# rc2014_6522.net
KiCad netlist of a schematic drawn in EAGLE
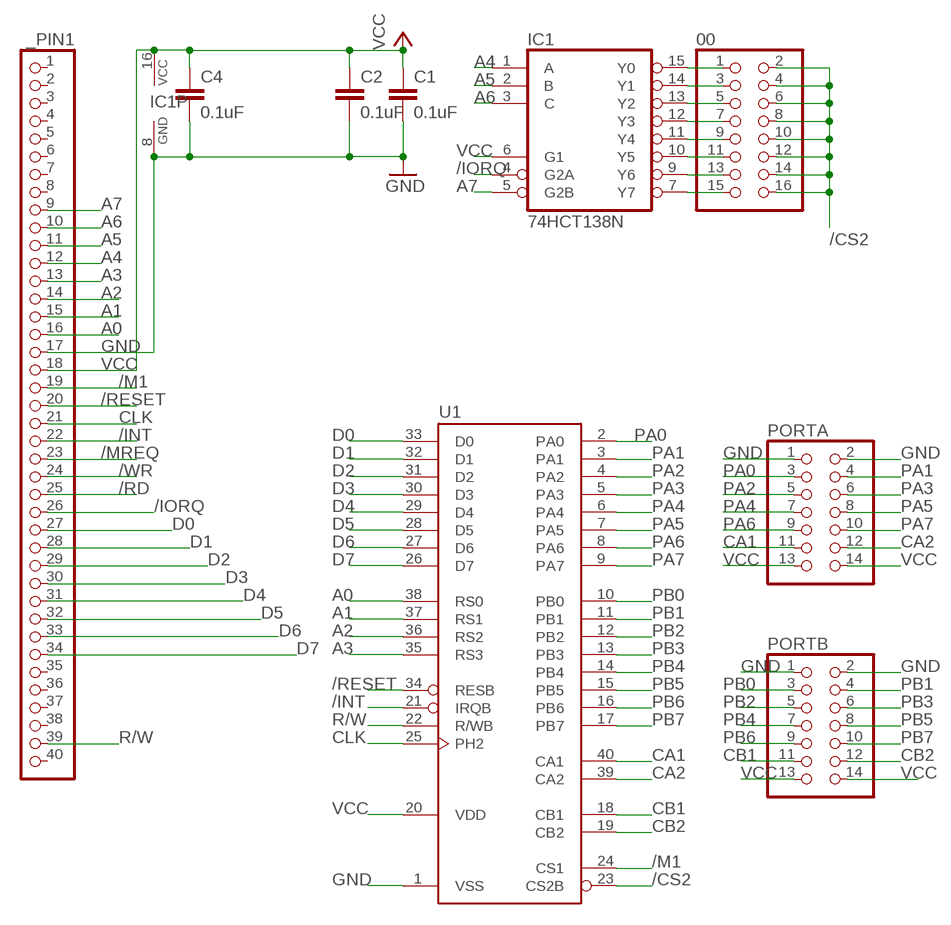
[diagram p0: schematic, sheet 1]

(export (version "E")
  (design (tool "Eeschema 10.0.6"))
  (components
    (comp (ref "00")
      (value "PINHD-2X8")
      (footprint "eagle-import:2X08")
      (libsource (lib "eagle-import") (part "PINHD-2X8"))
    )
    (comp (ref "C1")
      (value "0.1uF")
      (footprint "eagle-import:C050-024X044")
      (libsource (lib "eagle-import") (part "C-EU050-024X044"))
    )
    (comp (ref "C2")
      (value "0.1uF")
      (footprint "eagle-import:C050-024X044")
      (libsource (lib "eagle-import") (part "C-EU050-024X044"))
    )
    (comp (ref "C4")
      (value "0.1uF")
      (footprint "eagle-import:C050-024X044")
      (libsource (lib "eagle-import") (part "C-EU050-024X044"))
    )
    (comp (ref "IC1")
      (value "74HCT138N")
      (footprint "eagle-import:DIL16")
      (libsource (lib "eagle-import") (part "74138NHCT"))
    )
    (comp (ref "PORTA")
      (value "PINHD-2X7")
      (footprint "eagle-import:2X07")
      (libsource (lib "eagle-import") (part "PINHD-2X7"))
    )
    (comp (ref "PORTB")
      (value "PINHD-2X7")
      (footprint "eagle-import:2X07")
      (libsource (lib "eagle-import") (part "PINHD-2X7"))
    )
    (comp (ref "U1")
      (value "G65SC22P")
      (footprint "eagle-import:DIP-40")
      (libsource (lib "eagle-import") (part "G65SC22P"))
    )
    (comp (ref "_PIN1")
      (value "PINHD-1X40")
      (footprint "eagle-import:1X40")
      (libsource (lib "eagle-import") (part "PINHD-1X40"))
    )
  )
  (nets
    (net (code "1") (name "/A0") (class "Default")
      (node (ref "U1") (pin "38") (pinfunction "RS0_38") (pintype "input"))
      (node (ref "_PIN1") (pin "16") (pinfunction "16_16") (pintype "passive"))
    )
    (net (code "2") (name "/A1") (class "Default")
      (node (ref "U1") (pin "37") (pinfunction "RS1_37") (pintype "input"))
      (node (ref "_PIN1") (pin "15") (pinfunction "15_15") (pintype "passive"))
    )
    (net (code "3") (name "/A2") (class "Default")
      (node (ref "U1") (pin "36") (pinfunction "RS2_36") (pintype "input"))
      (node (ref "_PIN1") (pin "14") (pinfunction "14_14") (pintype "passive"))
    )
    (net (code "4") (name "/A3") (class "Default")
      (node (ref "U1") (pin "35") (pinfunction "RS3_35") (pintype "input"))
      (node (ref "_PIN1") (pin "13") (pinfunction "13_13") (pintype "passive"))
    )
    (net (code "5") (name "/A4") (class "Default")
      (node (ref "IC1") (pin "1") (pinfunction "A_1") (pintype "input"))
      (node (ref "_PIN1") (pin "12") (pinfunction "12_12") (pintype "passive"))
    )
    (net (code "6") (name "/A5") (class "Default")
      (node (ref "IC1") (pin "2") (pinfunction "B_2") (pintype "input"))
      (node (ref "_PIN1") (pin "11") (pinfunction "11_11") (pintype "passive"))
    )
    (net (code "7") (name "/A6") (class "Default")
      (node (ref "IC1") (pin "3") (pinfunction "C_3") (pintype "input"))
      (node (ref "_PIN1") (pin "10") (pinfunction "10_10") (pintype "passive"))
    )
    (net (code "8") (name "/A7") (class "Default")
      (node (ref "IC1") (pin "5") (pinfunction "G2B_5") (pintype "input"))
      (node (ref "_PIN1") (pin "9") (pinfunction "9_9") (pintype "passive"))
    )
    (net (code "9") (name "/CA1") (class "Default")
      (node (ref "PORTA") (pin "11") (pinfunction "11_11") (pintype "passive"))
      (node (ref "U1") (pin "40") (pinfunction "CA1_40") (pintype "bidirectional"))
    )
    (net (code "10") (name "/CA2") (class "Default")
      (node (ref "PORTA") (pin "12") (pinfunction "12_12") (pintype "passive"))
      (node (ref "U1") (pin "39") (pinfunction "CA2_39") (pintype "bidirectional"))
    )
    (net (code "11") (name "/CB1") (class "Default")
      (node (ref "PORTB") (pin "11") (pinfunction "11_11") (pintype "passive"))
      (node (ref "U1") (pin "18") (pinfunction "CB1_18") (pintype "bidirectional"))
    )
    (net (code "12") (name "/CB2") (class "Default")
      (node (ref "PORTB") (pin "12") (pinfunction "12_12") (pintype "passive"))
      (node (ref "U1") (pin "19") (pinfunction "CB2_19") (pintype "bidirectional"))
    )
    (net (code "13") (name "/CLK") (class "Default")
      (node (ref "U1") (pin "25") (pinfunction "PH2_25") (pintype "input"))
      (node (ref "_PIN1") (pin "21") (pinfunction "21_21") (pintype "passive"))
    )
    (net (code "14") (name "/D0") (class "Default")
      (node (ref "U1") (pin "33") (pinfunction "D0_33") (pintype "bidirectional"))
      (node (ref "_PIN1") (pin "27") (pinfunction "27_27") (pintype "passive"))
    )
    (net (code "15") (name "/D1") (class "Default")
      (node (ref "U1") (pin "32") (pinfunction "D1_32") (pintype "bidirectional"))
      (node (ref "_PIN1") (pin "28") (pinfunction "28_28") (pintype "passive"))
    )
    (net (code "16") (name "/D2") (class "Default")
      (node (ref "U1") (pin "31") (pinfunction "D2_31") (pintype "bidirectional"))
      (node (ref "_PIN1") (pin "29") (pinfunction "29_29") (pintype "passive"))
    )
    (net (code "17") (name "/D3") (class "Default")
      (node (ref "U1") (pin "30") (pinfunction "D3_30") (pintype "bidirectional"))
      (node (ref "_PIN1") (pin "30") (pinfunction "30_30") (pintype "passive"))
    )
    (net (code "18") (name "/D4") (class "Default")
      (node (ref "U1") (pin "29") (pinfunction "D4_29") (pintype "bidirectional"))
      (node (ref "_PIN1") (pin "31") (pinfunction "31_31") (pintype "passive"))
    )
    (net (code "19") (name "/D5") (class "Default")
      (node (ref "U1") (pin "28") (pinfunction "D5_28") (pintype "bidirectional"))
      (node (ref "_PIN1") (pin "32") (pinfunction "32_32") (pintype "passive"))
    )
    (net (code "20") (name "/D6") (class "Default")
      (node (ref "U1") (pin "27") (pinfunction "D6_27") (pintype "bidirectional"))
      (node (ref "_PIN1") (pin "33") (pinfunction "33_33") (pintype "passive"))
    )
    (net (code "21") (name "/D7") (class "Default")
      (node (ref "U1") (pin "26") (pinfunction "D7_26") (pintype "bidirectional"))
      (node (ref "_PIN1") (pin "34") (pinfunction "34_34") (pintype "passive"))
    )
    (net (code "22") (name "/PA0") (class "Default")
      (node (ref "PORTA") (pin "3") (pinfunction "3_3") (pintype "passive"))
      (node (ref "U1") (pin "2") (pinfunction "PA0_2") (pintype "bidirectional"))
    )
    (net (code "23") (name "/PA1") (class "Default")
      (node (ref "PORTA") (pin "4") (pinfunction "4_4") (pintype "passive"))
      (node (ref "U1") (pin "3") (pinfunction "PA1_3") (pintype "bidirectional"))
    )
    (net (code "24") (name "/PA2") (class "Default")
      (node (ref "PORTA") (pin "5") (pinfunction "5_5") (pintype "passive"))
      (node (ref "U1") (pin "4") (pinfunction "PA2_4") (pintype "bidirectional"))
    )
    (net (code "25") (name "/PA3") (class "Default")
      (node (ref "PORTA") (pin "6") (pinfunction "6_6") (pintype "passive"))
      (node (ref "U1") (pin "5") (pinfunction "PA3_5") (pintype "bidirectional"))
    )
    (net (code "26") (name "/PA4") (class "Default")
      (node (ref "PORTA") (pin "7") (pinfunction "7_7") (pintype "passive"))
      (node (ref "U1") (pin "6") (pinfunction "PA4_6") (pintype "bidirectional"))
    )
    (net (code "27") (name "/PA5") (class "Default")
      (node (ref "PORTA") (pin "8") (pinfunction "8_8") (pintype "passive"))
      (node (ref "U1") (pin "7") (pinfunction "PA5_7") (pintype "bidirectional"))
    )
    (net (code "28") (name "/PA6") (class "Default")
      (node (ref "PORTA") (pin "9") (pinfunction "9_9") (pintype "passive"))
      (node (ref "U1") (pin "8") (pinfunction "PA6_8") (pintype "bidirectional"))
    )
    (net (code "29") (name "/PA7") (class "Default")
      (node (ref "PORTA") (pin "10") (pinfunction "10_10") (pintype "passive"))
      (node (ref "U1") (pin "9") (pinfunction "PA7_9") (pintype "bidirectional"))
    )
    (net (code "30") (name "/PB0") (class "Default")
      (node (ref "PORTB") (pin "3") (pinfunction "3_3") (pintype "passive"))
      (node (ref "U1") (pin "10") (pinfunction "PB0_10") (pintype "bidirectional"))
    )
    (net (code "31") (name "/PB1") (class "Default")
      (node (ref "PORTB") (pin "4") (pinfunction "4_4") (pintype "passive"))
      (node (ref "U1") (pin "11") (pinfunction "PB1_11") (pintype "bidirectional"))
    )
    (net (code "32") (name "/PB2") (class "Default")
      (node (ref "PORTB") (pin "5") (pinfunction "5_5") (pintype "passive"))
      (node (ref "U1") (pin "12") (pinfunction "PB2_12") (pintype "bidirectional"))
    )
    (net (code "33") (name "/PB3") (class "Default")
      (node (ref "PORTB") (pin "6") (pinfunction "6_6") (pintype "passive"))
      (node (ref "U1") (pin "13") (pinfunction "PB3_13") (pintype "bidirectional"))
    )
    (net (code "34") (name "/PB4") (class "Default")
      (node (ref "PORTB") (pin "7") (pinfunction "7_7") (pintype "passive"))
      (node (ref "U1") (pin "14") (pinfunction "PB4_14") (pintype "bidirectional"))
    )
    (net (code "35") (name "/PB5") (class "Default")
      (node (ref "PORTB") (pin "8") (pinfunction "8_8") (pintype "passive"))
      (node (ref "U1") (pin "15") (pinfunction "PB5_15") (pintype "bidirectional"))
    )
    (net (code "36") (name "/PB6") (class "Default")
      (node (ref "PORTB") (pin "9") (pinfunction "9_9") (pintype "passive"))
      (node (ref "U1") (pin "16") (pinfunction "PB6_16") (pintype "bidirectional"))
    )
    (net (code "37") (name "/PB7") (class "Default")
      (node (ref "PORTB") (pin "10") (pinfunction "10_10") (pintype "passive"))
      (node (ref "U1") (pin "17") (pinfunction "PB7_17") (pintype "bidirectional"))
    )
    (net (code "38") (name "/R{slash}W") (class "Default")
      (node (ref "U1") (pin "22") (pinfunction "R/WB_22") (pintype "input"))
      (node (ref "_PIN1") (pin "39") (pinfunction "39_39") (pintype "passive"))
    )
    (net (code "39") (name "/{slash}CS2") (class "Default")
      (node (ref "00") (pin "10") (pinfunction "10_10") (pintype "passive"))
      (node (ref "00") (pin "12") (pinfunction "12_12") (pintype "passive"))
      (node (ref "00") (pin "14") (pinfunction "14_14") (pintype "passive"))
      (node (ref "00") (pin "16") (pinfunction "16_16") (pintype "passive"))
      (node (ref "00") (pin "2") (pinfunction "2_2") (pintype "passive"))
      (node (ref "00") (pin "4") (pinfunction "4_4") (pintype "passive"))
      (node (ref "00") (pin "6") (pinfunction "6_6") (pintype "passive"))
      (node (ref "00") (pin "8") (pinfunction "8_8") (pintype "passive"))
      (node (ref "U1") (pin "23") (pinfunction "CS2B_23") (pintype "input"))
    )
    (net (code "40") (name "/{slash}INT") (class "Default")
      (node (ref "U1") (pin "21") (pinfunction "IRQB_21") (pintype "output"))
      (node (ref "_PIN1") (pin "22") (pinfunction "22_22") (pintype "passive"))
    )
    (net (code "41") (name "/{slash}IORQ") (class "Default")
      (node (ref "IC1") (pin "4") (pinfunction "G2A_4") (pintype "input"))
      (node (ref "_PIN1") (pin "26") (pinfunction "26_26") (pintype "passive"))
    )
    (net (code "42") (name "/{slash}M1") (class "Default")
      (node (ref "U1") (pin "24") (pinfunction "CS1_24") (pintype "input"))
      (node (ref "_PIN1") (pin "19") (pinfunction "19_19") (pintype "passive"))
    )
    (net (code "43") (name "/{slash}MREQ") (class "Default")
      (node (ref "_PIN1") (pin "23") (pinfunction "23_23") (pintype "passive"))
    )
    (net (code "44") (name "/{slash}RD") (class "Default")
      (node (ref "_PIN1") (pin "25") (pinfunction "25_25") (pintype "passive"))
    )
    (net (code "45") (name "/{slash}RESET") (class "Default")
      (node (ref "U1") (pin "34") (pinfunction "RESB_34") (pintype "input"))
      (node (ref "_PIN1") (pin "20") (pinfunction "20_20") (pintype "passive"))
    )
    (net (code "46") (name "/{slash}WR") (class "Default")
      (node (ref "_PIN1") (pin "24") (pinfunction "24_24") (pintype "passive"))
    )
    (net (code "47") (name "GND") (class "Default")
      (node (ref "C1") (pin "2") (pinfunction "2_2") (pintype "passive"))
      (node (ref "C2") (pin "2") (pinfunction "2_2") (pintype "passive"))
      (node (ref "C4") (pin "2") (pinfunction "2_2") (pintype "passive"))
      (node (ref "IC1") (pin "8") (pinfunction "GND_8") (pintype "power_in"))
      (node (ref "PORTA") (pin "1") (pinfunction "1_1") (pintype "passive"))
      (node (ref "PORTA") (pin "2") (pinfunction "2_2") (pintype "passive"))
      (node (ref "PORTB") (pin "1") (pinfunction "1_1") (pintype "passive"))
      (node (ref "PORTB") (pin "2") (pinfunction "2_2") (pintype "passive"))
      (node (ref "U1") (pin "1") (pinfunction "VSS_1") (pintype "power_in"))
      (node (ref "_PIN1") (pin "17") (pinfunction "17_17") (pintype "passive"))
    )
    (net (code "48") (name "Net-(IC1A-Y0)") (class "Default")
      (node (ref "00") (pin "1") (pinfunction "1_1") (pintype "passive"))
      (node (ref "IC1") (pin "15") (pinfunction "Y0_15") (pintype "output"))
    )
    (net (code "49") (name "Net-(IC1A-Y1)") (class "Default")
      (node (ref "00") (pin "3") (pinfunction "3_3") (pintype "passive"))
      (node (ref "IC1") (pin "14") (pinfunction "Y1_14") (pintype "output"))
    )
    (net (code "50") (name "Net-(IC1A-Y2)") (class "Default")
      (node (ref "00") (pin "5") (pinfunction "5_5") (pintype "passive"))
      (node (ref "IC1") (pin "13") (pinfunction "Y2_13") (pintype "output"))
    )
    (net (code "51") (name "Net-(IC1A-Y3)") (class "Default")
      (node (ref "00") (pin "7") (pinfunction "7_7") (pintype "passive"))
      (node (ref "IC1") (pin "12") (pinfunction "Y3_12") (pintype "output"))
    )
    (net (code "52") (name "Net-(IC1A-Y4)") (class "Default")
      (node (ref "00") (pin "9") (pinfunction "9_9") (pintype "passive"))
      (node (ref "IC1") (pin "11") (pinfunction "Y4_11") (pintype "output"))
    )
    (net (code "53") (name "Net-(IC1A-Y5)") (class "Default")
      (node (ref "00") (pin "11") (pinfunction "11_11") (pintype "passive"))
      (node (ref "IC1") (pin "10") (pinfunction "Y5_10") (pintype "output"))
    )
    (net (code "54") (name "Net-(IC1A-Y6)") (class "Default")
      (node (ref "00") (pin "13") (pinfunction "13_13") (pintype "passive"))
      (node (ref "IC1") (pin "9") (pinfunction "Y6_9") (pintype "output"))
    )
    (net (code "55") (name "Net-(IC1A-Y7)") (class "Default")
      (node (ref "00") (pin "15") (pinfunction "15_15") (pintype "passive"))
      (node (ref "IC1") (pin "7") (pinfunction "Y7_7") (pintype "output"))
    )
    (net (code "56") (name "VCC") (class "Default")
      (node (ref "C1") (pin "1") (pinfunction "1_1") (pintype "passive"))
      (node (ref "C2") (pin "1") (pinfunction "1_1") (pintype "passive"))
      (node (ref "C4") (pin "1") (pinfunction "1_1") (pintype "passive"))
      (node (ref "IC1") (pin "16") (pinfunction "VCC_16") (pintype "power_in"))
      (node (ref "IC1") (pin "6") (pinfunction "G1_6") (pintype "input"))
      (node (ref "PORTA") (pin "13") (pinfunction "13_13") (pintype "passive"))
      (node (ref "PORTA") (pin "14") (pinfunction "14_14") (pintype "passive"))
      (node (ref "PORTB") (pin "13") (pinfunction "13_13") (pintype "passive"))
      (node (ref "PORTB") (pin "14") (pinfunction "14_14") (pintype "passive"))
      (node (ref "U1") (pin "20") (pinfunction "VDD_20") (pintype "power_in"))
      (node (ref "_PIN1") (pin "18") (pinfunction "18_18") (pintype "passive"))
    )
    (net (code "57") (name "unconnected-(_PIN1-Pad1)") (class "Default")
      (node (ref "_PIN1") (pin "1") (pinfunction "1_1") (pintype "passive"))
    )
    (net (code "58") (name "unconnected-(_PIN1-Pad2)") (class "Default")
      (node (ref "_PIN1") (pin "2") (pinfunction "2_2") (pintype "passive"))
    )
    (net (code "59") (name "unconnected-(_PIN1-Pad3)") (class "Default")
      (node (ref "_PIN1") (pin "3") (pinfunction "3_3") (pintype "passive"))
    )
    (net (code "60") (name "unconnected-(_PIN1-Pad4)") (class "Default")
      (node (ref "_PIN1") (pin "4") (pinfunction "4_4") (pintype "passive"))
    )
    (net (code "61") (name "unconnected-(_PIN1-Pad5)") (class "Default")
      (node (ref "_PIN1") (pin "5") (pinfunction "5_5") (pintype "passive"))
    )
    (net (code "62") (name "unconnected-(_PIN1-Pad6)") (class "Default")
      (node (ref "_PIN1") (pin "6") (pinfunction "6_6") (pintype "passive"))
    )
    (net (code "63") (name "unconnected-(_PIN1-Pad7)") (class "Default")
      (node (ref "_PIN1") (pin "7") (pinfunction "7_7") (pintype "passive"))
    )
    (net (code "64") (name "unconnected-(_PIN1-Pad8)") (class "Default")
      (node (ref "_PIN1") (pin "8") (pinfunction "8_8") (pintype "passive"))
    )
    (net (code "65") (name "unconnected-(_PIN1-Pad35)") (class "Default")
      (node (ref "_PIN1") (pin "35") (pinfunction "35_35") (pintype "passive"))
    )
    (net (code "66") (name "unconnected-(_PIN1-Pad36)") (class "Default")
      (node (ref "_PIN1") (pin "36") (pinfunction "36_36") (pintype "passive"))
    )
    (net (code "67") (name "unconnected-(_PIN1-Pad37)") (class "Default")
      (node (ref "_PIN1") (pin "37") (pinfunction "37_37") (pintype "passive"))
    )
    (net (code "68") (name "unconnected-(_PIN1-Pad38)") (class "Default")
      (node (ref "_PIN1") (pin "38") (pinfunction "38_38") (pintype "passive"))
    )
    (net (code "69") (name "unconnected-(_PIN1-Pad40)") (class "Default")
      (node (ref "_PIN1") (pin "40") (pinfunction "40_40") (pintype "passive"))
    )
  )
)
